# 03_-_POWER.net
KiCad netlist of a schematic drawn in Altium Designer
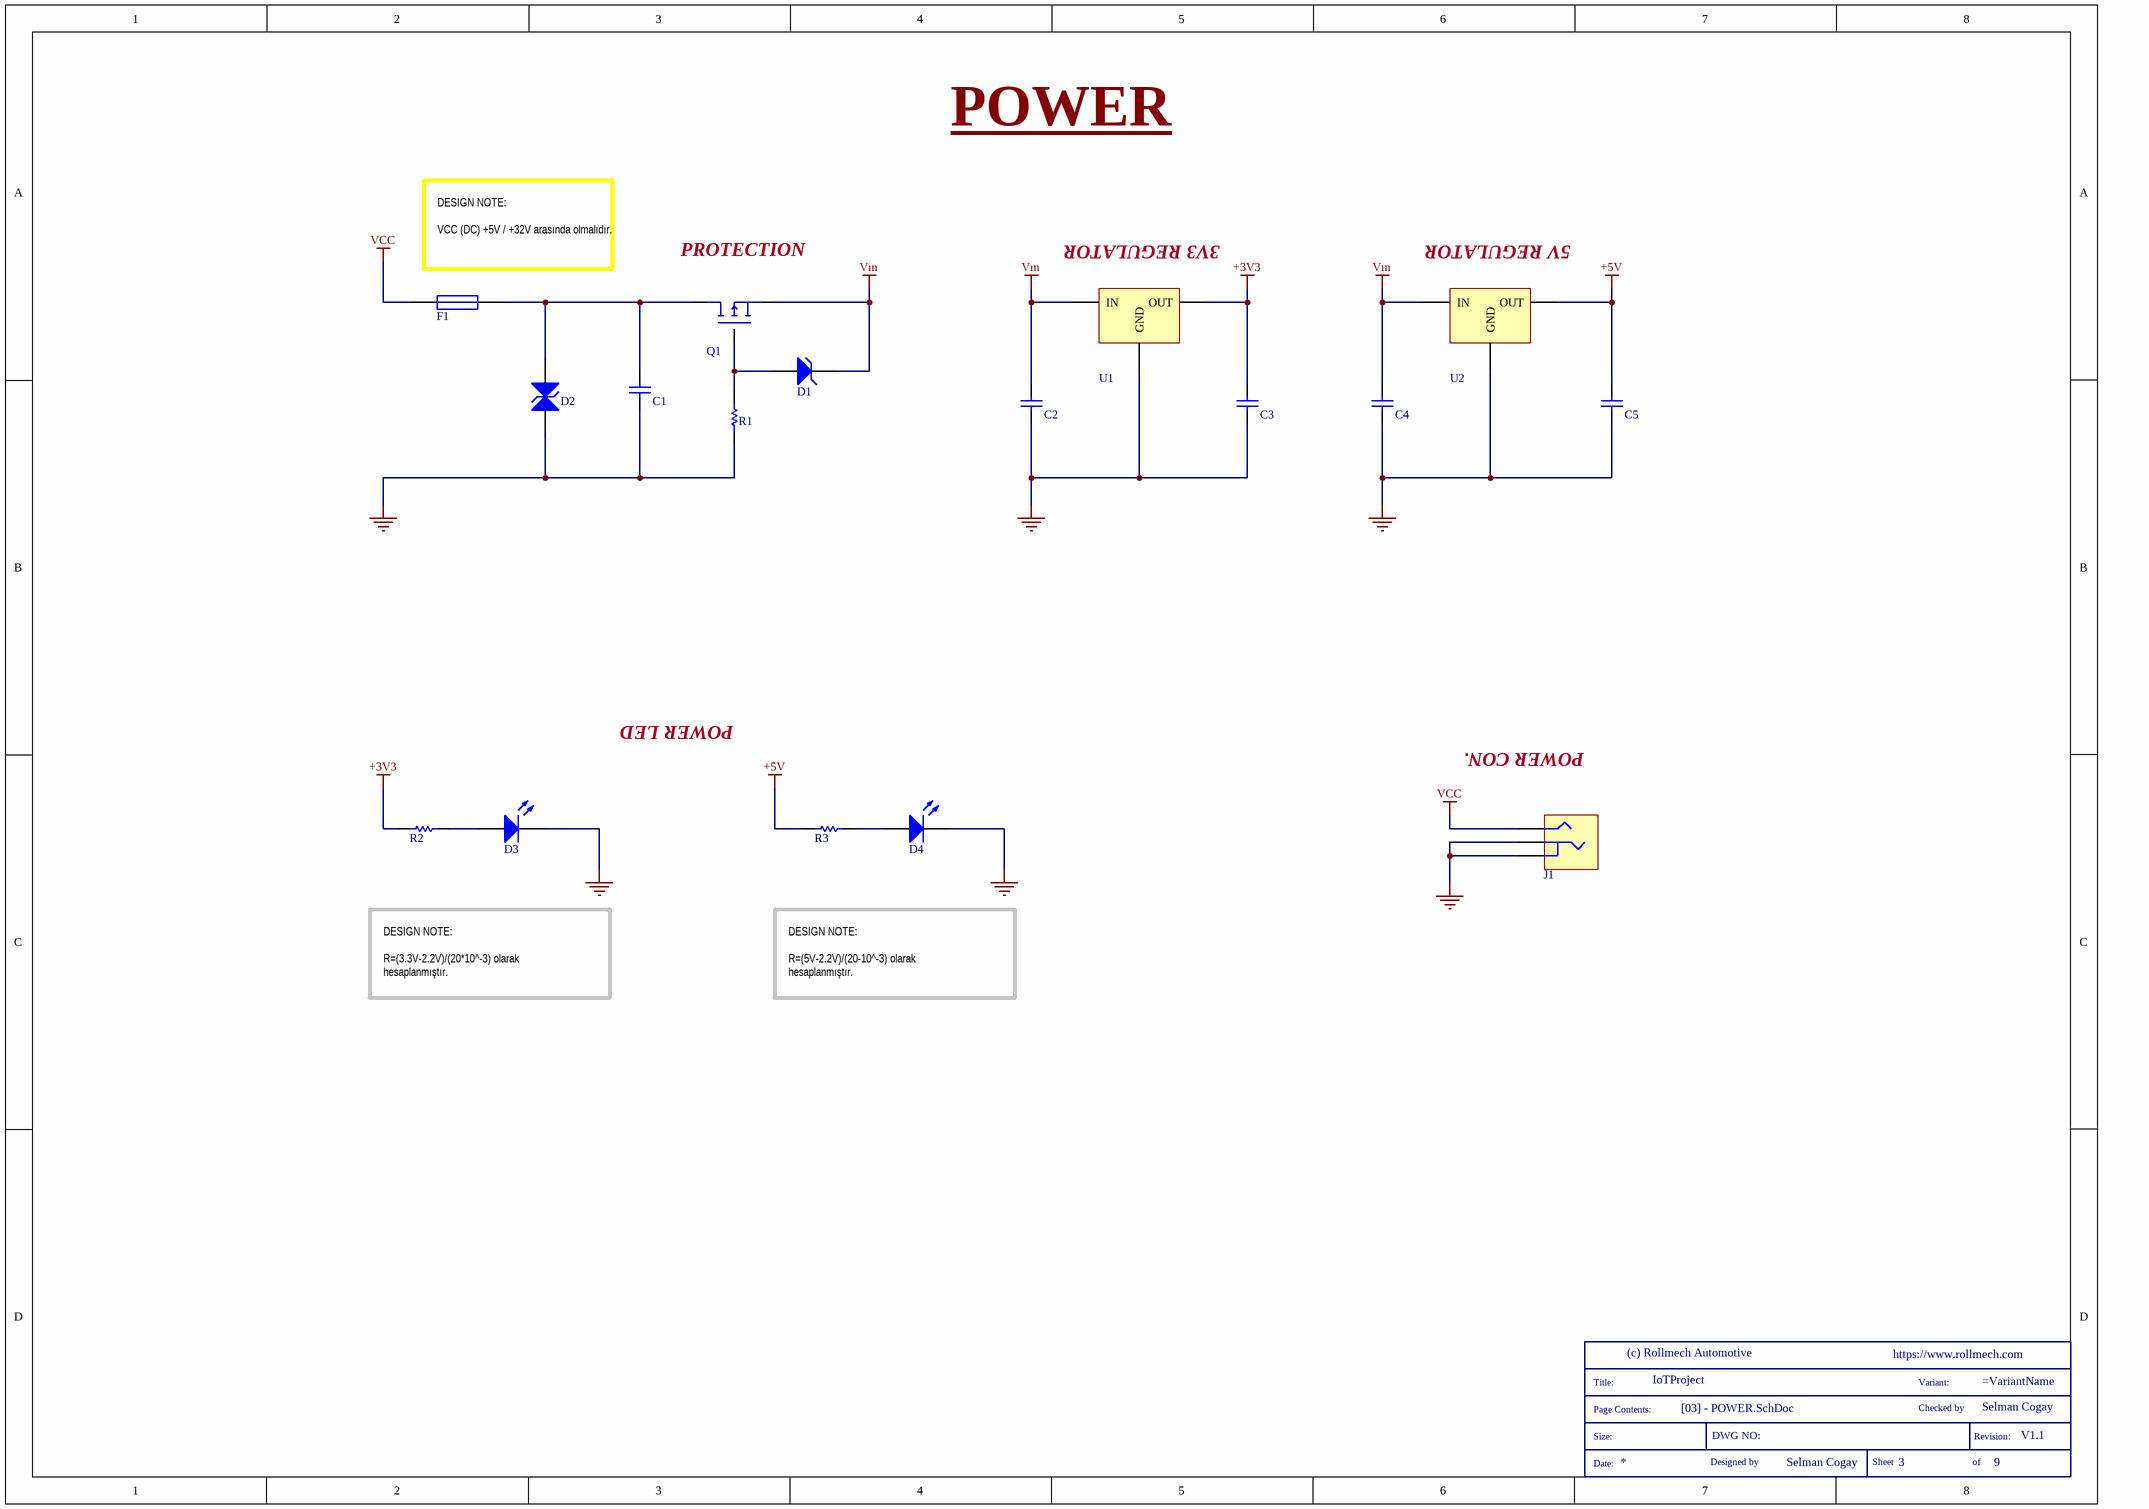
[diagram p0: [03] - POWER.SchDoc]

(export (version "E")
  (design (tool "Eeschema 10.0.6"))
  (components
    (comp (ref "C1")
      (value "1uF 35V")
      (footprint "C0603")
      (description "CAP CER 1UF 35V")
      (libsource (lib "Rollmech_Altium") (part "CGA3E3X5R1V105K080AB"))
    )
    (comp (ref "C2")
      (value "100nF 35V")
      (footprint "CAP_CER_0603")
      (description "CAP CER 100nf 35V X5R 0603")
      (libsource (lib "Rollmech_Altium") (part "GMK107BJ104KAHT"))
    )
    (comp (ref "C3")
      (value "10uF 16V")
      (footprint "CAP_CER_0805")
      (description "CAP CER 10UF 16V")
      (libsource (lib "Rollmech_Altium") (part "CGA4J1X5R1C106M125AC"))
    )
    (comp (ref "C4")
      (value "100nF 35V")
      (footprint "CAP_CER_0603")
      (description "CAP CER 100nf 35V X5R 0603")
      (libsource (lib "Rollmech_Altium") (part "GMK107BJ104KAHT"))
    )
    (comp (ref "C5")
      (value "10uF 16V")
      (footprint "CAP_CER_0805")
      (description "CAP CER 10UF 16V")
      (libsource (lib "Rollmech_Altium") (part "CGA4J1X5R1C106M125AC"))
    )
    (comp (ref "D1")
      (value "12V 250mW")
      (footprint "SOT-23 (TO-236)")
      (description "DIODE ZENER 12V 250MW")
      (libsource (lib "Rollmech_Altium") (part "SZBZX84C12LT1G"))
    )
    (comp (ref "D2")
      (value "33V3")
      (footprint "DO-214AB")
      (description "TVS DIODE 30.8V 49.9V SMB")
      (libsource (lib "Rollmech_Altium") (part "SZP6SMB36CAT3G"))
    )
    (comp (ref "D3")
      (value "LED RED")
      (footprint "PLCC2")
      (description "LED TOPLED RED 626NM 2PLCC")
      (libsource (lib "Rollmech_Altium") (part "LR T67D-U1V2-1-1-20-R18-Z"))
    )
    (comp (ref "D4")
      (value "LED RED")
      (footprint "PLCC2")
      (description "LED TOPLED RED 626NM 2PLCC")
      (libsource (lib "Rollmech_Altium") (part "LR T67D-U1V2-1-1-20-R18-Z"))
    )
    (comp (ref "F1")
      (value "1.25A 32VDC")
      (footprint "FUSE_0603")
      (description "FUSE 1.25A 32VDC 0603")
      (libsource (lib "Rollmech_Altium") (part "MFU0603FF01250P100"))
    )
    (comp (ref "J1")
      (value "CONN 2x5.5 Jack")
      (footprint "POWER_JACK")
      (description "CONN PWR JACK 2X5.5MM SOLDER")
      (libsource (lib "Rollmech_Altium") (part "PJ-002A"))
    )
    (comp (ref "Q1")
      (value "PNP 60V 36A")
      (footprint "PowerPak-SO8")
      (description "MOSFET P-CH 60V 36A")
      (libsource (lib "Rollmech_Altium") (part "SQJ457EP-T1_GE3"))
    )
    (comp (ref "R1")
      (value "100K 1/4W")
      (footprint "RES_0603")
      (description "RES SMD 100K 5% 1/4W 0603")
      (libsource (lib "Rollmech_Altium") (part "ERJ-PA3J104V"))
    )
    (comp (ref "R2")
      (value "54.9 1/8W")
      (footprint "RES_0805")
      (description "RES SMD 54.9 OHM")
      (libsource (lib "Rollmech_Altium") (part "ERJ-6ENF54R9V"))
    )
    (comp (ref "R3")
      (value "140 1/8W")
      (footprint "RES_0805")
      (description "RES SMD 140 OHM 1% 1/8W 0805")
      (libsource (lib "Rollmech_Altium") (part "ERJ-6ENF1400V"))
    )
    (comp (ref "U1")
      (value "TLE4284DV33")
      (footprint "PG-TO252-3-11")
      (description "IC REG LINEAR 3.3V 1A")
      (libsource (lib "Rollmech_Altium") (part "TLE4284DV33ATMA1"))
    )
    (comp (ref "U2")
      (value "TLE4284DV50")
      (footprint "PG-TO252-3-11")
      (description "IC REG LINEAR 5V 1A")
      (libsource (lib "Rollmech_Altium") (part "TLE4284DV50ATMA1"))
    )
  )
  (nets
    (net (code "1") (name "+3V3") (class "Default")
      (node (ref "C3") (pin "2") (pinfunction "2_2") (pintype "passive"))
      (node (ref "R2") (pin "1") (pinfunction "1_1") (pintype "passive"))
      (node (ref "U1") (pin "2") (pinfunction "OUT_2") (pintype "passive"))
    )
    (net (code "2") (name "+5V") (class "Default")
      (node (ref "C5") (pin "2") (pinfunction "2_2") (pintype "passive"))
      (node (ref "R3") (pin "1") (pinfunction "1_1") (pintype "passive"))
      (node (ref "U2") (pin "2") (pinfunction "OUT_2") (pintype "passive"))
    )
    (net (code "3") (name "GND") (class "Default")
      (node (ref "C1") (pin "1") (pinfunction "1_1") (pintype "passive"))
      (node (ref "C2") (pin "1") (pinfunction "1_1") (pintype "passive"))
      (node (ref "C3") (pin "1") (pinfunction "1_1") (pintype "passive"))
      (node (ref "C4") (pin "1") (pinfunction "1_1") (pintype "passive"))
      (node (ref "C5") (pin "1") (pinfunction "1_1") (pintype "passive"))
      (node (ref "D2") (pin "1") (pinfunction "A_1") (pintype "passive"))
      (node (ref "D3") (pin "2") (pinfunction "K_2") (pintype "passive"))
      (node (ref "D4") (pin "2") (pinfunction "K_2") (pintype "passive"))
      (node (ref "J1") (pin "2") (pinfunction "2_2") (pintype "passive"))
      (node (ref "J1") (pin "3") (pinfunction "3_3") (pintype "passive"))
      (node (ref "R1") (pin "1") (pinfunction "1_1") (pintype "passive"))
      (node (ref "U1") (pin "1") (pinfunction "GND_1") (pintype "passive"))
      (node (ref "U2") (pin "1") (pinfunction "GND_1") (pintype "passive"))
    )
    (net (code "4") (name "Net-(D1-A)") (class "Default")
      (node (ref "D1") (pin "2") (pinfunction "A_2") (pintype "passive"))
      (node (ref "Q1") (pin "4") (pinfunction "G_4") (pintype "passive"))
      (node (ref "R1") (pin "2") (pinfunction "2_2") (pintype "passive"))
    )
    (net (code "5") (name "Net-(D2-K)") (class "Default")
      (node (ref "C1") (pin "2") (pinfunction "2_2") (pintype "passive"))
      (node (ref "D2") (pin "2") (pinfunction "K_2") (pintype "passive"))
      (node (ref "F1") (pin "2") (pinfunction "2_2") (pintype "passive"))
      (node (ref "Q1") (pin "5") (pinfunction "D_5") (pintype "passive"))
    )
    (net (code "6") (name "Net-(D3-A)") (class "Default")
      (node (ref "D3") (pin "1") (pinfunction "A_1") (pintype "passive"))
      (node (ref "R2") (pin "2") (pinfunction "2_2") (pintype "passive"))
    )
    (net (code "7") (name "Net-(D4-A)") (class "Default")
      (node (ref "D4") (pin "1") (pinfunction "A_1") (pintype "passive"))
      (node (ref "R3") (pin "2") (pinfunction "2_2") (pintype "passive"))
    )
    (net (code "8") (name "VCC") (class "Default")
      (node (ref "F1") (pin "1") (pinfunction "1_1") (pintype "passive"))
      (node (ref "J1") (pin "1") (pinfunction "1_1") (pintype "passive"))
    )
    (net (code "9") (name "Vın") (class "Default")
      (node (ref "C2") (pin "2") (pinfunction "2_2") (pintype "passive"))
      (node (ref "C4") (pin "2") (pinfunction "2_2") (pintype "passive"))
      (node (ref "D1") (pin "3") (pinfunction "K_3") (pintype "passive"))
      (node (ref "Q1") (pin "1") (pinfunction "S_1") (pintype "passive"))
      (node (ref "U1") (pin "3") (pinfunction "IN_3") (pintype "passive"))
      (node (ref "U2") (pin "3") (pinfunction "IN_3") (pintype "passive"))
    )
  )
)
